# interceptor.net
KiCad netlist of a schematic drawn in EAGLE
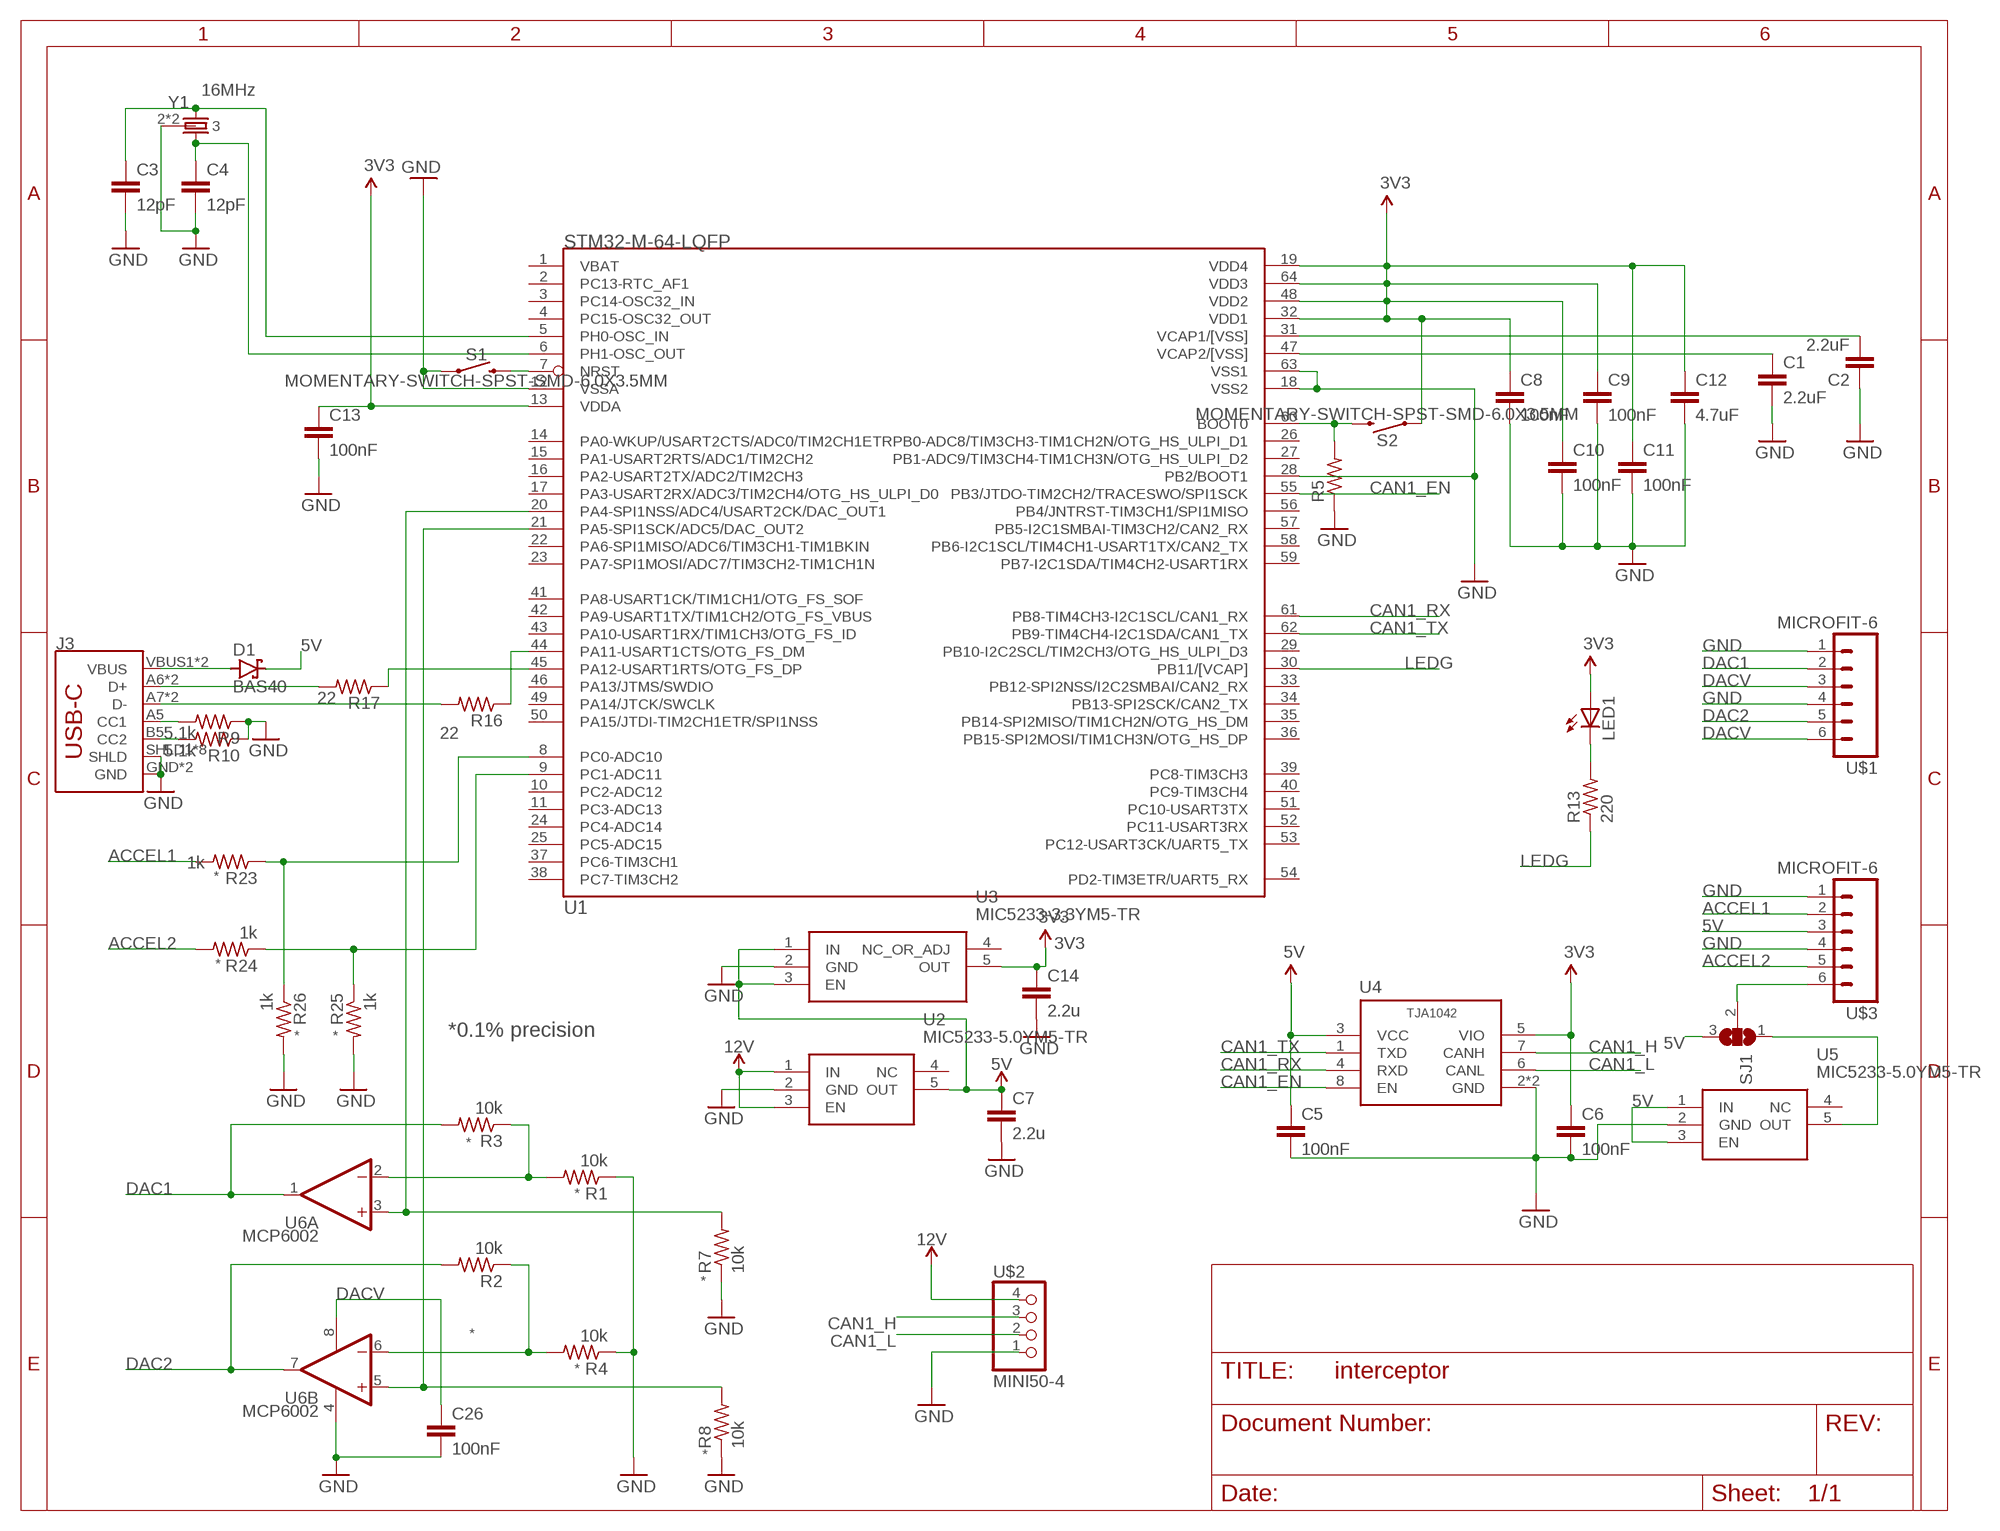
[diagram p0: schematic, sheet 1]

(export (version "E")
  (design (tool "Eeschema 10.0.6"))
  (components
    (comp (ref "C1")
      (value "2.2uF")
      (footprint "eagle-import:0603-C")
      (libsource (lib "eagle-import") (part "C0603"))
    )
    (comp (ref "C2")
      (value "2.2uF")
      (footprint "eagle-import:0603-C")
      (libsource (lib "eagle-import") (part "C0603"))
    )
    (comp (ref "C3")
      (value "12pF")
      (footprint "eagle-import:0603-C")
      (libsource (lib "eagle-import") (part "C0603"))
    )
    (comp (ref "C4")
      (value "12pF")
      (footprint "eagle-import:0603-C")
      (libsource (lib "eagle-import") (part "C0603"))
    )
    (comp (ref "C5")
      (value "100nF")
      (footprint "eagle-import:0603-C")
      (libsource (lib "eagle-import") (part "C0603"))
    )
    (comp (ref "C6")
      (value "100nF")
      (footprint "eagle-import:0603-C")
      (libsource (lib "eagle-import") (part "C0603"))
    )
    (comp (ref "C7")
      (value "2.2u")
      (footprint "eagle-import:C0603")
      (libsource (lib "eagle-import") (part "C-EUC0603"))
    )
    (comp (ref "C8")
      (value "100nF")
      (footprint "eagle-import:0603-C")
      (libsource (lib "eagle-import") (part "C0603"))
    )
    (comp (ref "C9")
      (value "100nF")
      (footprint "eagle-import:0603-C")
      (libsource (lib "eagle-import") (part "C0603"))
    )
    (comp (ref "C10")
      (value "100nF")
      (footprint "eagle-import:0603-C")
      (libsource (lib "eagle-import") (part "C0603"))
    )
    (comp (ref "C11")
      (value "100nF")
      (footprint "eagle-import:0603-C")
      (libsource (lib "eagle-import") (part "C0603"))
    )
    (comp (ref "C12")
      (value "4.7uF")
      (footprint "eagle-import:0603-C")
      (libsource (lib "eagle-import") (part "C0603"))
    )
    (comp (ref "C13")
      (value "100nF")
      (footprint "eagle-import:0603-C")
      (libsource (lib "eagle-import") (part "C0603"))
    )
    (comp (ref "C14")
      (value "2.2u")
      (footprint "eagle-import:C0603")
      (libsource (lib "eagle-import") (part "C-EUC0603"))
    )
    (comp (ref "C26")
      (value "100nF")
      (footprint "eagle-import:0603-C")
      (libsource (lib "eagle-import") (part "C0603"))
    )
    (comp (ref "D1")
      (value "BAS40")
      (footprint "eagle-import:SOT23")
      (libsource (lib "eagle-import") (part "BAS40"))
    )
    (comp (ref "J3")
      (value "USB-C-BREAKOUT_SPARKFUN-CONNECTORS_USB_C16PIN")
      (footprint "eagle-import:USB-C-BREAKOUT_SPARKFUN-CONNECTORS_USB-C-16P")
      (libsource (lib "eagle-import") (part "USB-C-BREAKOUT_SPARKFUN-CONNECTORS_USB_C16PIN"))
    )
    (comp (ref "LED1")
      (value "LEDCHIPLED_0805")
      (footprint "eagle-import:CHIPLED_0805")
      (libsource (lib "eagle-import") (part "LEDCHIPLED_0805"))
    )
    (comp (ref "R1")
      (value "10k")
      (footprint "eagle-import:0402-R")
      (libsource (lib "eagle-import") (part "R0402"))
    )
    (comp (ref "R2")
      (value "10k")
      (footprint "eagle-import:0402-R")
      (libsource (lib "eagle-import") (part "R0402"))
    )
    (comp (ref "R3")
      (value "10k")
      (footprint "eagle-import:0402-R")
      (libsource (lib "eagle-import") (part "R0402"))
    )
    (comp (ref "R4")
      (value "10k")
      (footprint "eagle-import:0402-R")
      (libsource (lib "eagle-import") (part "R0402"))
    )
    (comp (ref "R5")
      (value "R0402")
      (footprint "eagle-import:0402-R")
      (libsource (lib "eagle-import") (part "R0402"))
    )
    (comp (ref "R7")
      (value "10k")
      (footprint "eagle-import:0402-R")
      (libsource (lib "eagle-import") (part "R0402"))
    )
    (comp (ref "R8")
      (value "10k")
      (footprint "eagle-import:0402-R")
      (libsource (lib "eagle-import") (part "R0402"))
    )
    (comp (ref "R9")
      (value "5.1k")
      (footprint "eagle-import:0402-R")
      (libsource (lib "eagle-import") (part "R0402"))
    )
    (comp (ref "R10")
      (value "5.1k")
      (footprint "eagle-import:0402-R")
      (libsource (lib "eagle-import") (part "R0402"))
    )
    (comp (ref "R13")
      (value "220")
      (footprint "eagle-import:0402-R")
      (libsource (lib "eagle-import") (part "R0402"))
    )
    (comp (ref "R16")
      (value "22")
      (footprint "eagle-import:0402-R")
      (libsource (lib "eagle-import") (part "R0402"))
    )
    (comp (ref "R17")
      (value "22")
      (footprint "eagle-import:0402-R")
      (libsource (lib "eagle-import") (part "R0402"))
    )
    (comp (ref "R23")
      (value "1k")
      (footprint "eagle-import:0402-R")
      (libsource (lib "eagle-import") (part "R0402"))
    )
    (comp (ref "R24")
      (value "1k")
      (footprint "eagle-import:0402-R")
      (libsource (lib "eagle-import") (part "R0402"))
    )
    (comp (ref "R25")
      (value "1k")
      (footprint "eagle-import:0402-R")
      (libsource (lib "eagle-import") (part "R0402"))
    )
    (comp (ref "R26")
      (value "1k")
      (footprint "eagle-import:0402-R")
      (libsource (lib "eagle-import") (part "R0402"))
    )
    (comp (ref "S1")
      (value "MOMENTARY-SWITCH-SPST-SMD-6.0X3.5MM")
      (footprint "eagle-import:TACTILE_SWITCH_SMD_6.0X3.5MM")
      (libsource (lib "eagle-import") (part "MOMENTARY-SWITCH-SPST-SMD-6.0X3.5MM"))
    )
    (comp (ref "S2")
      (value "MOMENTARY-SWITCH-SPST-SMD-6.0X3.5MM")
      (footprint "eagle-import:TACTILE_SWITCH_SMD_6.0X3.5MM")
      (libsource (lib "eagle-import") (part "MOMENTARY-SWITCH-SPST-SMD-6.0X3.5MM"))
    )
    (comp (ref "SJ1")
      (value "SJ2W")
      (footprint "eagle-import:SJ_2")
      (libsource (lib "eagle-import") (part "SJ2W"))
    )
    (comp (ref "U$1")
      (value "MICROFIT-6")
      (footprint "eagle-import:MICROFIT-6")
      (libsource (lib "eagle-import") (part "MICROFIT-6"))
    )
    (comp (ref "U$2")
      (value "MINI50-4")
      (footprint "eagle-import:MINI50")
      (libsource (lib "eagle-import") (part "MINI50-4"))
    )
    (comp (ref "U$3")
      (value "MICROFIT-6")
      (footprint "eagle-import:MICROFIT-6")
      (libsource (lib "eagle-import") (part "MICROFIT-6"))
    )
    (comp (ref "U1")
      (value "STM32-M-64-LQFP")
      (footprint "eagle-import:LQFP64")
      (libsource (lib "eagle-import") (part "STM32-M-64-LQFP"))
    )
    (comp (ref "U2")
      (value "MIC5233-5.0YM5-TR")
      (footprint "eagle-import:SOT95P280X145-5N")
      (fields (field (name "MOUSER_PART_NUMBER") "998-MIC5233-5.0YM5TR"))
      (libsource (lib "eagle-import") (part "MIC5233-5.0YM5-TR"))
    )
    (comp (ref "U3")
      (value "MIC5233-3.3YM5-TR")
      (footprint "eagle-import:SOT95P280X145-5N")
      (fields (field (name "MOUSER_PART_NUMBER") "998-MIC5233-3.3YM5TR"))
      (libsource (lib "eagle-import") (part "MIC5233-3.3YM5-TR"))
    )
    (comp (ref "U4")
      (value "TJA1042HVSON")
      (footprint "eagle-import:HVSON8")
      (libsource (lib "eagle-import") (part "TJA1042HVSON"))
    )
    (comp (ref "U5")
      (value "MIC5233-5.0YM5-TR")
      (footprint "eagle-import:SOT95P280X145-5N")
      (fields (field (name "MOUSER_PART_NUMBER") "998-MIC5233-5.0YM5TR"))
      (libsource (lib "eagle-import") (part "MIC5233-5.0YM5-TR"))
    )
    (comp (ref "U6")
      (value "MCP6002")
      (footprint "eagle-import:SO08")
      (libsource (lib "eagle-import") (part "LM358D"))
    )
    (comp (ref "Y1")
      (value "16MHz")
      (footprint "eagle-import:XTAL-3.2X2.5")
      (libsource (lib "eagle-import") (part "CRYSTAL-3.2X2.54-PIN"))
    )
  )
  (nets
    (net (code "1") (name "/ACCEL1") (class "Default")
      (node (ref "R23") (pin "2") (pinfunction "2_2") (pintype "passive"))
      (node (ref "U$3") (pin "2") (pinfunction "2_2") (pintype "passive"))
    )
    (net (code "2") (name "/ACCEL2") (class "Default")
      (node (ref "R24") (pin "2") (pinfunction "2_2") (pintype "passive"))
      (node (ref "U$3") (pin "5") (pinfunction "5_5") (pintype "passive"))
    )
    (net (code "3") (name "/CAN1_EN") (class "Default")
      (node (ref "U1") (pin "55") (pinfunction "PB3/JTDO-TIM2CH2/TRACESWO/SPI1SCK_55") (pintype "bidirectional"))
      (node (ref "U4") (pin "8") (pinfunction "EN_8") (pintype "bidirectional"))
    )
    (net (code "4") (name "/CAN1_H") (class "Default")
      (node (ref "U$2") (pin "3") (pinfunction "2_3") (pintype "passive"))
      (node (ref "U4") (pin "7") (pinfunction "CANH_7") (pintype "bidirectional"))
    )
    (net (code "5") (name "/CAN1_L") (class "Default")
      (node (ref "U$2") (pin "2") (pinfunction "3_2") (pintype "passive"))
      (node (ref "U4") (pin "6") (pinfunction "CANL_6") (pintype "bidirectional"))
    )
    (net (code "6") (name "/CAN1_RX") (class "Default")
      (node (ref "U1") (pin "61") (pinfunction "PB8-TIM4CH3-I2C1SCL/CAN1_RX_61") (pintype "bidirectional"))
      (node (ref "U4") (pin "4") (pinfunction "RXD_4") (pintype "bidirectional"))
    )
    (net (code "7") (name "/CAN1_TX") (class "Default")
      (node (ref "U1") (pin "62") (pinfunction "PB9-TIM4CH4-I2C1SDA/CAN1_TX_62") (pintype "bidirectional"))
      (node (ref "U4") (pin "1") (pinfunction "TXD_1") (pintype "bidirectional"))
    )
    (net (code "8") (name "/DAC1") (class "Default")
      (node (ref "R3") (pin "2") (pinfunction "2_2") (pintype "passive"))
      (node (ref "U$1") (pin "2") (pinfunction "2_2") (pintype "passive"))
      (node (ref "U6") (pin "1") (pinfunction "OUT_1") (pintype "output"))
    )
    (net (code "9") (name "/DAC2") (class "Default")
      (node (ref "R2") (pin "2") (pinfunction "2_2") (pintype "passive"))
      (node (ref "U$1") (pin "5") (pinfunction "5_5") (pintype "passive"))
      (node (ref "U6") (pin "7") (pinfunction "OUT_7") (pintype "output"))
    )
    (net (code "10") (name "/DACV") (class "Default")
      (node (ref "C26") (pin "1") (pinfunction "1_1") (pintype "passive"))
      (node (ref "U$1") (pin "3") (pinfunction "3_3") (pintype "passive"))
      (node (ref "U$1") (pin "6") (pinfunction "6_6") (pintype "passive"))
      (node (ref "U6") (pin "8") (pinfunction "V+_8") (pintype "power_in"))
    )
    (net (code "11") (name "/LEDG") (class "Default")
      (node (ref "R13") (pin "1") (pinfunction "1_1") (pintype "passive"))
      (node (ref "U1") (pin "30") (pinfunction "PB11/[VCAP]_30") (pintype "bidirectional"))
    )
    (net (code "12") (name "/VBAT") (class "Default")
      (node (ref "U1") (pin "1") (pinfunction "VBAT_1") (pintype "power_in"))
    )
    (net (code "13") (name "3V3") (class "Default")
      (node (ref "C10") (pin "1") (pinfunction "1_1") (pintype "passive"))
      (node (ref "C11") (pin "1") (pinfunction "1_1") (pintype "passive"))
      (node (ref "C12") (pin "1") (pinfunction "1_1") (pintype "passive"))
      (node (ref "C13") (pin "1") (pinfunction "1_1") (pintype "passive"))
      (node (ref "C14") (pin "1") (pinfunction "1_1") (pintype "passive"))
      (node (ref "C6") (pin "1") (pinfunction "1_1") (pintype "passive"))
      (node (ref "C8") (pin "1") (pinfunction "1_1") (pintype "passive"))
      (node (ref "C9") (pin "1") (pinfunction "1_1") (pintype "passive"))
      (node (ref "LED1") (pin "A") (pinfunction "A_A") (pintype "passive"))
      (node (ref "S2") (pin "1") (pinfunction "1_1") (pintype "passive"))
      (node (ref "U1") (pin "13") (pinfunction "VDDA_13") (pintype "power_in"))
      (node (ref "U1") (pin "19") (pinfunction "VDD4_19") (pintype "bidirectional"))
      (node (ref "U1") (pin "32") (pinfunction "VDD1_32") (pintype "power_in"))
      (node (ref "U1") (pin "48") (pinfunction "VDD2_48") (pintype "power_in"))
      (node (ref "U1") (pin "64") (pinfunction "VDD3_64") (pintype "power_in"))
      (node (ref "U3") (pin "5") (pinfunction "OUT_5") (pintype "bidirectional"))
      (node (ref "U4") (pin "5") (pinfunction "VIO_5") (pintype "bidirectional"))
    )
    (net (code "14") (name "5V") (class "Default")
      (node (ref "C5") (pin "1") (pinfunction "1_1") (pintype "passive"))
      (node (ref "C7") (pin "1") (pinfunction "1_1") (pintype "passive"))
      (node (ref "D1") (pin "3") (pinfunction "C_3") (pintype "passive"))
      (node (ref "SJ1") (pin "3") (pinfunction "3_3") (pintype "passive"))
      (node (ref "U$3") (pin "3") (pinfunction "3_3") (pintype "passive"))
      (node (ref "U2") (pin "5") (pinfunction "OUT_5") (pintype "bidirectional"))
      (node (ref "U3") (pin "1") (pinfunction "IN_1") (pintype "bidirectional"))
      (node (ref "U3") (pin "3") (pinfunction "EN_3") (pintype "bidirectional"))
      (node (ref "U4") (pin "3") (pinfunction "VCC_3") (pintype "bidirectional"))
      (node (ref "U5") (pin "1") (pinfunction "IN_1") (pintype "bidirectional"))
      (node (ref "U5") (pin "3") (pinfunction "EN_3") (pintype "bidirectional"))
    )
    (net (code "15") (name "12V") (class "Default")
      (node (ref "U$2") (pin "4") (pinfunction "1_4") (pintype "passive"))
      (node (ref "U2") (pin "1") (pinfunction "IN_1") (pintype "bidirectional"))
      (node (ref "U2") (pin "3") (pinfunction "EN_3") (pintype "bidirectional"))
    )
    (net (code "16") (name "GND") (class "Default")
      (node (ref "C1") (pin "2") (pinfunction "2_2") (pintype "passive"))
      (node (ref "C10") (pin "2") (pinfunction "2_2") (pintype "passive"))
      (node (ref "C11") (pin "2") (pinfunction "2_2") (pintype "passive"))
      (node (ref "C12") (pin "2") (pinfunction "2_2") (pintype "passive"))
      (node (ref "C13") (pin "2") (pinfunction "2_2") (pintype "passive"))
      (node (ref "C14") (pin "2") (pinfunction "2_2") (pintype "passive"))
      (node (ref "C2") (pin "1") (pinfunction "1_1") (pintype "passive"))
      (node (ref "C26") (pin "2") (pinfunction "2_2") (pintype "passive"))
      (node (ref "C3") (pin "2") (pinfunction "2_2") (pintype "passive"))
      (node (ref "C4") (pin "2") (pinfunction "2_2") (pintype "passive"))
      (node (ref "C5") (pin "2") (pinfunction "2_2") (pintype "passive"))
      (node (ref "C6") (pin "2") (pinfunction "2_2") (pintype "passive"))
      (node (ref "C7") (pin "2") (pinfunction "2_2") (pintype "passive"))
      (node (ref "C8") (pin "2") (pinfunction "2_2") (pintype "passive"))
      (node (ref "C9") (pin "2") (pinfunction "2_2") (pintype "passive"))
      (node (ref "J3") (pin "GND") (pinfunction "GND_GND") (pintype "bidirectional"))
      (node (ref "J3") (pin "GND2") (pinfunction "GND_GND2") (pintype "bidirectional"))
      (node (ref "J3") (pin "SHLD1") (pinfunction "SHLD_SHLD1") (pintype "bidirectional"))
      (node (ref "J3") (pin "SHLD2") (pinfunction "SHLD_SHLD2") (pintype "bidirectional"))
      (node (ref "J3") (pin "SHLD3") (pinfunction "SHLD_SHLD3") (pintype "bidirectional"))
      (node (ref "J3") (pin "SHLD4") (pinfunction "SHLD_SHLD4") (pintype "bidirectional"))
      (node (ref "J3") (pin "SHLD5") (pinfunction "SHLD_SHLD5") (pintype "bidirectional"))
      (node (ref "J3") (pin "SHLD6") (pinfunction "SHLD_SHLD6") (pintype "bidirectional"))
      (node (ref "J3") (pin "SHLD7") (pinfunction "SHLD_SHLD7") (pintype "bidirectional"))
      (node (ref "J3") (pin "SHLD8") (pinfunction "SHLD_SHLD8") (pintype "bidirectional"))
      (node (ref "R1") (pin "1") (pinfunction "1_1") (pintype "passive"))
      (node (ref "R10") (pin "1") (pinfunction "1_1") (pintype "passive"))
      (node (ref "R25") (pin "2") (pinfunction "2_2") (pintype "passive"))
      (node (ref "R26") (pin "2") (pinfunction "2_2") (pintype "passive"))
      (node (ref "R4") (pin "1") (pinfunction "1_1") (pintype "passive"))
      (node (ref "R5") (pin "1") (pinfunction "1_1") (pintype "passive"))
      (node (ref "R7") (pin "1") (pinfunction "1_1") (pintype "passive"))
      (node (ref "R8") (pin "1") (pinfunction "1_1") (pintype "passive"))
      (node (ref "R9") (pin "1") (pinfunction "1_1") (pintype "passive"))
      (node (ref "S1") (pin "1") (pinfunction "1_1") (pintype "passive"))
      (node (ref "U$1") (pin "1") (pinfunction "1_1") (pintype "passive"))
      (node (ref "U$1") (pin "4") (pinfunction "4_4") (pintype "passive"))
      (node (ref "U$2") (pin "1") (pinfunction "4_1") (pintype "passive"))
      (node (ref "U$3") (pin "1") (pinfunction "1_1") (pintype "passive"))
      (node (ref "U$3") (pin "4") (pinfunction "4_4") (pintype "passive"))
      (node (ref "U1") (pin "12") (pinfunction "VSSA_12") (pintype "power_in"))
      (node (ref "U1") (pin "18") (pinfunction "VSS2_18") (pintype "bidirectional"))
      (node (ref "U1") (pin "28") (pinfunction "PB2/BOOT1_28") (pintype "bidirectional"))
      (node (ref "U1") (pin "63") (pinfunction "VSS1_63") (pintype "power_in"))
      (node (ref "U2") (pin "2") (pinfunction "GND_2") (pintype "bidirectional"))
      (node (ref "U3") (pin "2") (pinfunction "GND_2") (pintype "bidirectional"))
      (node (ref "U4") (pin "2") (pinfunction "GND_2") (pintype "bidirectional"))
      (node (ref "U4") (pin "PAD") (pinfunction "GND_PAD") (pintype "bidirectional"))
      (node (ref "U5") (pin "2") (pinfunction "GND_2") (pintype "bidirectional"))
      (node (ref "U6") (pin "4") (pinfunction "V-_4") (pintype "power_in"))
      (node (ref "Y1") (pin "2") (pinfunction "3_2") (pintype "bidirectional"))
      (node (ref "Y1") (pin "4") (pinfunction "3_4") (pintype "bidirectional"))
    )
    (net (code "17") (name "Net-(D1-A)") (class "Default")
      (node (ref "D1") (pin "1") (pinfunction "A_1") (pintype "passive"))
      (node (ref "J3") (pin "VBUS1") (pinfunction "VBUS_VBUS1") (pintype "bidirectional"))
      (node (ref "J3") (pin "VBUS2") (pinfunction "VBUS_VBUS2") (pintype "bidirectional"))
    )
    (net (code "18") (name "Net-(J3-CC1)") (class "Default")
      (node (ref "J3") (pin "A5") (pinfunction "CC1_A5") (pintype "bidirectional"))
      (node (ref "R9") (pin "2") (pinfunction "2_2") (pintype "passive"))
    )
    (net (code "19") (name "Net-(J3-CC2)") (class "Default")
      (node (ref "J3") (pin "B5") (pinfunction "CC2_B5") (pintype "bidirectional"))
      (node (ref "R10") (pin "2") (pinfunction "2_2") (pintype "passive"))
    )
    (net (code "20") (name "Net-(J3-D+-PadA6)") (class "Default")
      (node (ref "J3") (pin "A6") (pinfunction "D+_A6") (pintype "bidirectional"))
      (node (ref "J3") (pin "B6") (pinfunction "D+_B6") (pintype "bidirectional"))
      (node (ref "R17") (pin "2") (pinfunction "2_2") (pintype "passive"))
    )
    (net (code "21") (name "Net-(J3-D--PadA7)") (class "Default")
      (node (ref "J3") (pin "A7") (pinfunction "D-_A7") (pintype "bidirectional"))
      (node (ref "J3") (pin "B7") (pinfunction "D-_B7") (pintype "bidirectional"))
      (node (ref "R16") (pin "2") (pinfunction "2_2") (pintype "passive"))
    )
    (net (code "22") (name "Net-(LED1-PadC)") (class "Default")
      (node (ref "LED1") (pin "C") (pinfunction "C_C") (pintype "passive"))
      (node (ref "R13") (pin "2") (pinfunction "2_2") (pintype "passive"))
    )
    (net (code "23") (name "Net-(SJ1-Pad2)") (class "Default")
      (node (ref "SJ1") (pin "2") (pinfunction "2_2") (pintype "passive"))
      (node (ref "U$3") (pin "6") (pinfunction "6_6") (pintype "passive"))
    )
    (net (code "24") (name "Net-(U1-BOOT0)") (class "Default")
      (node (ref "R5") (pin "2") (pinfunction "2_2") (pintype "passive"))
      (node (ref "S2") (pin "2") (pinfunction "2_2") (pintype "passive"))
      (node (ref "U1") (pin "60") (pinfunction "BOOT0_60") (pintype "input"))
    )
    (net (code "25") (name "Net-(U1-NRST)") (class "Default")
      (node (ref "S1") (pin "2") (pinfunction "2_2") (pintype "passive"))
      (node (ref "U1") (pin "7") (pinfunction "NRST_7") (pintype "bidirectional"))
    )
    (net (code "26") (name "Net-(U1-PA4-SPI1NSS{slash}ADC4{slash}USART2CK{slash}DAC_OUT1)") (class "Default")
      (node (ref "R7") (pin "2") (pinfunction "2_2") (pintype "passive"))
      (node (ref "U1") (pin "20") (pinfunction "PA4-SPI1NSS/ADC4/USART2CK/DAC_OUT1_20") (pintype "bidirectional"))
      (node (ref "U6") (pin "3") (pinfunction "+IN_3") (pintype "input"))
    )
    (net (code "27") (name "Net-(U1-PA5-SPI1SCK{slash}ADC5{slash}DAC_OUT2)") (class "Default")
      (node (ref "R8") (pin "2") (pinfunction "2_2") (pintype "passive"))
      (node (ref "U1") (pin "21") (pinfunction "PA5-SPI1SCK/ADC5/DAC_OUT2_21") (pintype "bidirectional"))
      (node (ref "U6") (pin "5") (pinfunction "+IN_5") (pintype "input"))
    )
    (net (code "28") (name "Net-(U1-PA11-USART1CTS{slash}OTG_FS_DM)") (class "Default")
      (node (ref "R16") (pin "1") (pinfunction "1_1") (pintype "passive"))
      (node (ref "U1") (pin "44") (pinfunction "PA11-USART1CTS/OTG_FS_DM_44") (pintype "bidirectional"))
    )
    (net (code "29") (name "Net-(U1-PA12-USART1RTS{slash}OTG_FS_DP)") (class "Default")
      (node (ref "R17") (pin "1") (pinfunction "1_1") (pintype "passive"))
      (node (ref "U1") (pin "45") (pinfunction "PA12-USART1RTS/OTG_FS_DP_45") (pintype "bidirectional"))
    )
    (net (code "30") (name "Net-(U1-PC0-ADC10)") (class "Default")
      (node (ref "R23") (pin "1") (pinfunction "1_1") (pintype "passive"))
      (node (ref "R26") (pin "1") (pinfunction "1_1") (pintype "passive"))
      (node (ref "U1") (pin "8") (pinfunction "PC0-ADC10_8") (pintype "bidirectional"))
    )
    (net (code "31") (name "Net-(U1-PC1-ADC11)") (class "Default")
      (node (ref "R24") (pin "1") (pinfunction "1_1") (pintype "passive"))
      (node (ref "R25") (pin "1") (pinfunction "1_1") (pintype "passive"))
      (node (ref "U1") (pin "9") (pinfunction "PC1-ADC11_9") (pintype "bidirectional"))
    )
    (net (code "32") (name "Net-(U1-PH0-OSC_IN)") (class "Default")
      (node (ref "C3") (pin "1") (pinfunction "1_1") (pintype "passive"))
      (node (ref "U1") (pin "5") (pinfunction "PH0-OSC_IN_5") (pintype "input"))
      (node (ref "Y1") (pin "1") (pinfunction "1_1") (pintype "passive"))
    )
    (net (code "33") (name "Net-(U1-PH1-OSC_OUT)") (class "Default")
      (node (ref "C4") (pin "1") (pinfunction "1_1") (pintype "passive"))
      (node (ref "U1") (pin "6") (pinfunction "PH1-OSC_OUT_6") (pintype "output"))
      (node (ref "Y1") (pin "3") (pinfunction "2_3") (pintype "passive"))
    )
    (net (code "34") (name "Net-(U1-VCAP1{slash}[VSS])") (class "Default")
      (node (ref "C2") (pin "2") (pinfunction "2_2") (pintype "passive"))
      (node (ref "U1") (pin "31") (pinfunction "VCAP1/[VSS]_31") (pintype "power_in"))
    )
    (net (code "35") (name "Net-(U1-VCAP2{slash}[VSS])") (class "Default")
      (node (ref "C1") (pin "1") (pinfunction "1_1") (pintype "passive"))
      (node (ref "U1") (pin "47") (pinfunction "VCAP2/[VSS]_47") (pintype "power_in"))
    )
    (net (code "36") (name "Net-(U5-OUT)") (class "Default")
      (node (ref "SJ1") (pin "1") (pinfunction "1_1") (pintype "passive"))
      (node (ref "U5") (pin "5") (pinfunction "OUT_5") (pintype "bidirectional"))
    )
    (net (code "37") (name "Net-(U6A--IN)") (class "Default")
      (node (ref "R1") (pin "2") (pinfunction "2_2") (pintype "passive"))
      (node (ref "R3") (pin "1") (pinfunction "1_1") (pintype "passive"))
      (node (ref "U6") (pin "2") (pinfunction "-IN_2") (pintype "input"))
    )
    (net (code "38") (name "Net-(U6B--IN)") (class "Default")
      (node (ref "R2") (pin "1") (pinfunction "1_1") (pintype "passive"))
      (node (ref "R4") (pin "2") (pinfunction "2_2") (pintype "passive"))
      (node (ref "U6") (pin "6") (pinfunction "-IN_6") (pintype "input"))
    )
    (net (code "39") (name "unconnected-(U1-PA0-WKUP{slash}USART2CTS{slash}ADC0{slash}TIM2CH1ETR-Pad14)") (class "Default")
      (node (ref "U1") (pin "14") (pinfunction "PA0-WKUP/USART2CTS/ADC0/TIM2CH1ETR_14") (pintype "bidirectional"))
    )
    (net (code "40") (name "unconnected-(U1-PA1-USART2RTS{slash}ADC1{slash}TIM2CH2-Pad15)") (class "Default")
      (node (ref "U1") (pin "15") (pinfunction "PA1-USART2RTS/ADC1/TIM2CH2_15") (pintype "bidirectional"))
    )
    (net (code "41") (name "unconnected-(U1-PA2-USART2TX{slash}ADC2{slash}TIM2CH3-Pad16)") (class "Default")
      (node (ref "U1") (pin "16") (pinfunction "PA2-USART2TX/ADC2/TIM2CH3_16") (pintype "bidirectional"))
    )
    (net (code "42") (name "unconnected-(U1-PA3-USART2RX{slash}ADC3{slash}TIM2CH4{slash}OTG_HS_ULPI_D0-Pad17)") (class "Default")
      (node (ref "U1") (pin "17") (pinfunction "PA3-USART2RX/ADC3/TIM2CH4/OTG_HS_ULPI_D0_17") (pintype "bidirectional"))
    )
    (net (code "43") (name "unconnected-(U1-PA6-SPI1MISO{slash}ADC6{slash}TIM3CH1-TIM1BKIN-Pad22)") (class "Default")
      (node (ref "U1") (pin "22") (pinfunction "PA6-SPI1MISO/ADC6/TIM3CH1-TIM1BKIN_22") (pintype "bidirectional"))
    )
    (net (code "44") (name "unconnected-(U1-PA7-SPI1MOSI{slash}ADC7{slash}TIM3CH2-TIM1CH1N-Pad23)") (class "Default")
      (node (ref "U1") (pin "23") (pinfunction "PA7-SPI1MOSI/ADC7/TIM3CH2-TIM1CH1N_23") (pintype "bidirectional"))
    )
    (net (code "45") (name "unconnected-(U1-PA8-USART1CK{slash}TIM1CH1{slash}OTG_FS_SOF-Pad41)") (class "Default")
      (node (ref "U1") (pin "41") (pinfunction "PA8-USART1CK/TIM1CH1/OTG_FS_SOF_41") (pintype "bidirectional"))
    )
    (net (code "46") (name "unconnected-(U1-PA9-USART1TX{slash}TIM1CH2{slash}OTG_FS_VBUS-Pad42)") (class "Default")
      (node (ref "U1") (pin "42") (pinfunction "PA9-USART1TX/TIM1CH2/OTG_FS_VBUS_42") (pintype "bidirectional"))
    )
    (net (code "47") (name "unconnected-(U1-PA10-USART1RX{slash}TIM1CH3{slash}OTG_FS_ID-Pad43)") (class "Default")
      (node (ref "U1") (pin "43") (pinfunction "PA10-USART1RX/TIM1CH3/OTG_FS_ID_43") (pintype "bidirectional"))
    )
    (net (code "48") (name "unconnected-(U1-PA13{slash}JTMS{slash}SWDIO-Pad46)") (class "Default")
      (node (ref "U1") (pin "46") (pinfunction "PA13/JTMS/SWDIO_46") (pintype "bidirectional"))
    )
    (net (code "49") (name "unconnected-(U1-PA14{slash}JTCK{slash}SWCLK-Pad49)") (class "Default")
      (node (ref "U1") (pin "49") (pinfunction "PA14/JTCK/SWCLK_49") (pintype "bidirectional"))
    )
    (net (code "50") (name "unconnected-(U1-PA15{slash}JTDI-TIM2CH1ETR{slash}SPI1NSS-Pad50)") (class "Default")
      (node (ref "U1") (pin "50") (pinfunction "PA15/JTDI-TIM2CH1ETR/SPI1NSS_50") (pintype "bidirectional"))
    )
    (net (code "51") (name "unconnected-(U1-PB0-ADC8{slash}TIM3CH3-TIM1CH2N{slash}OTG_HS_ULPI_D1-Pad26)") (class "Default")
      (node (ref "U1") (pin "26") (pinfunction "PB0-ADC8/TIM3CH3-TIM1CH2N/OTG_HS_ULPI_D1_26") (pintype "bidirectional"))
    )
    (net (code "52") (name "unconnected-(U1-PB1-ADC9{slash}TIM3CH4-TIM1CH3N{slash}OTG_HS_ULPI_D2-Pad27)") (class "Default")
      (node (ref "U1") (pin "27") (pinfunction "PB1-ADC9/TIM3CH4-TIM1CH3N/OTG_HS_ULPI_D2_27") (pintype "bidirectional"))
    )
    (net (code "53") (name "unconnected-(U1-PB4{slash}JNTRST-TIM3CH1{slash}SPI1MISO-Pad56)") (class "Default")
      (node (ref "U1") (pin "56") (pinfunction "PB4/JNTRST-TIM3CH1/SPI1MISO_56") (pintype "bidirectional"))
    )
    (net (code "54") (name "unconnected-(U1-PB5-I2C1SMBAI-TIM3CH2{slash}CAN2_RX-Pad57)") (class "Default")
      (node (ref "U1") (pin "57") (pinfunction "PB5-I2C1SMBAI-TIM3CH2/CAN2_RX_57") (pintype "bidirectional"))
    )
    (net (code "55") (name "unconnected-(U1-PB6-I2C1SCL{slash}TIM4CH1-USART1TX{slash}CAN2_TX-Pad58)") (class "Default")
      (node (ref "U1") (pin "58") (pinfunction "PB6-I2C1SCL/TIM4CH1-USART1TX/CAN2_TX_58") (pintype "bidirectional"))
    )
    (net (code "56") (name "unconnected-(U1-PB7-I2C1SDA{slash}TIM4CH2-USART1RX-Pad59)") (class "Default")
      (node (ref "U1") (pin "59") (pinfunction "PB7-I2C1SDA/TIM4CH2-USART1RX_59") (pintype "bidirectional"))
    )
    (net (code "57") (name "unconnected-(U1-PB10-I2C2SCL{slash}TIM2CH3{slash}OTG_HS_ULPI_D3-Pad29)") (class "Default")
      (node (ref "U1") (pin "29") (pinfunction "PB10-I2C2SCL/TIM2CH3/OTG_HS_ULPI_D3_29") (pintype "bidirectional"))
    )
    (net (code "58") (name "unconnected-(U1-PB12-SPI2NSS{slash}I2C2SMBAI{slash}CAN2_RX-Pad33)") (class "Default")
      (node (ref "U1") (pin "33") (pinfunction "PB12-SPI2NSS/I2C2SMBAI/CAN2_RX_33") (pintype "bidirectional"))
    )
    (net (code "59") (name "unconnected-(U1-PB13-SPI2SCK{slash}CAN2_TX-Pad34)") (class "Default")
      (node (ref "U1") (pin "34") (pinfunction "PB13-SPI2SCK/CAN2_TX_34") (pintype "bidirectional"))
    )
    (net (code "60") (name "unconnected-(U1-PB14-SPI2MISO{slash}TIM1CH2N{slash}OTG_HS_DM-Pad35)") (class "Default")
      (node (ref "U1") (pin "35") (pinfunction "PB14-SPI2MISO/TIM1CH2N/OTG_HS_DM_35") (pintype "bidirectional"))
    )
    (net (code "61") (name "unconnected-(U1-PB15-SPI2MOSI{slash}TIM1CH3N{slash}OTG_HS_DP-Pad36)") (class "Default")
      (node (ref "U1") (pin "36") (pinfunction "PB15-SPI2MOSI/TIM1CH3N/OTG_HS_DP_36") (pintype "bidirectional"))
    )
    (net (code "62") (name "unconnected-(U1-PC2-ADC12-Pad10)") (class "Default")
      (node (ref "U1") (pin "10") (pinfunction "PC2-ADC12_10") (pintype "bidirectional"))
    )
    (net (code "63") (name "unconnected-(U1-PC3-ADC13-Pad11)") (class "Default")
      (node (ref "U1") (pin "11") (pinfunction "PC3-ADC13_11") (pintype "bidirectional"))
    )
    (net (code "64") (name "unconnected-(U1-PC4-ADC14-Pad24)") (class "Default")
      (node (ref "U1") (pin "24") (pinfunction "PC4-ADC14_24") (pintype "bidirectional"))
    )
    (net (code "65") (name "unconnected-(U1-PC5-ADC15-Pad25)") (class "Default")
      (node (ref "U1") (pin "25") (pinfunction "PC5-ADC15_25") (pintype "bidirectional"))
    )
    (net (code "66") (name "unconnected-(U1-PC6-TIM3CH1-Pad37)") (class "Default")
      (node (ref "U1") (pin "37") (pinfunction "PC6-TIM3CH1_37") (pintype "bidirectional"))
    )
    (net (code "67") (name "unconnected-(U1-PC7-TIM3CH2-Pad38)") (class "Default")
      (node (ref "U1") (pin "38") (pinfunction "PC7-TIM3CH2_38") (pintype "bidirectional"))
    )
    (net (code "68") (name "unconnected-(U1-PC8-TIM3CH3-Pad39)") (class "Default")
      (node (ref "U1") (pin "39") (pinfunction "PC8-TIM3CH3_39") (pintype "bidirectional"))
    )
    (net (code "69") (name "unconnected-(U1-PC9-TIM3CH4-Pad40)") (class "Default")
      (node (ref "U1") (pin "40") (pinfunction "PC9-TIM3CH4_40") (pintype "bidirectional"))
    )
    (net (code "70") (name "unconnected-(U1-PC10-USART3TX-Pad51)") (class "Default")
      (node (ref "U1") (pin "51") (pinfunction "PC10-USART3TX_51") (pintype "bidirectional"))
    )
    (net (code "71") (name "unconnected-(U1-PC11-USART3RX-Pad52)") (class "Default")
      (node (ref "U1") (pin "52") (pinfunction "PC11-USART3RX_52") (pintype "bidirectional"))
    )
    (net (code "72") (name "unconnected-(U1-PC12-USART3CK{slash}UART5_TX-Pad53)") (class "Default")
      (node (ref "U1") (pin "53") (pinfunction "PC12-USART3CK/UART5_TX_53") (pintype "bidirectional"))
    )
    (net (code "73") (name "unconnected-(U1-PC13-RTC_AF1-Pad2)") (class "Default")
      (node (ref "U1") (pin "2") (pinfunction "PC13-RTC_AF1_2") (pintype "bidirectional"))
    )
    (net (code "74") (name "unconnected-(U1-PC14-OSC32_IN-Pad3)") (class "Default")
      (node (ref "U1") (pin "3") (pinfunction "PC14-OSC32_IN_3") (pintype "bidirectional"))
    )
    (net (code "75") (name "unconnected-(U1-PC15-OSC32_OUT-Pad4)") (class "Default")
      (node (ref "U1") (pin "4") (pinfunction "PC15-OSC32_OUT_4") (pintype "bidirectional"))
    )
    (net (code "76") (name "unconnected-(U1-PD2-TIM3ETR{slash}UART5_RX-Pad54)") (class "Default")
      (node (ref "U1") (pin "54") (pinfunction "PD2-TIM3ETR/UART5_RX_54") (pintype "bidirectional"))
    )
    (net (code "77") (name "unconnected-(U2-NC-Pad4)") (class "Default")
      (node (ref "U2") (pin "4") (pinfunction "NC_4") (pintype "no_connect"))
    )
    (net (code "78") (name "unconnected-(U3-NC_OR_ADJ-Pad4)") (class "Default")
      (node (ref "U3") (pin "4") (pinfunction "NC_OR_ADJ_4") (pintype "bidirectional"))
    )
    (net (code "79") (name "unconnected-(U5-NC-Pad4)") (class "Default")
      (node (ref "U5") (pin "4") (pinfunction "NC_4") (pintype "no_connect"))
    )
  )
)
